# GPS_Module.net
KiCad netlist of a schematic drawn in Altium Designer
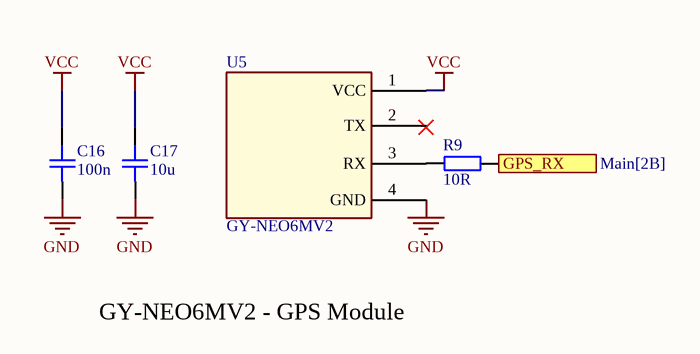
[diagram p0: GPS_Module.SchDoc]

(export (version "E")
  (design (tool "Eeschema 10.0.6"))
  (components
    (comp (ref "C16")
      (value "100n")
      (footprint "CAP_0805")
      (description "Capacitor SMD 0805")
      (libsource (lib "Schematic-Lib-PhilsLab") (part "CAP_0805"))
    )
    (comp (ref "C17")
      (value "10u")
      (footprint "CAP_0805")
      (description "Capacitor SMD 0805")
      (libsource (lib "Schematic-Lib-PhilsLab") (part "CAP_0805"))
    )
    (comp (ref "R9")
      (value "10R")
      (footprint "RES_0805")
      (description "Resistor SMD 0805")
      (libsource (lib "Schematic-Lib-PhilsLab") (part "RES_0805"))
    )
    (comp (ref "U5")
      (value "GY-NEO6MV2")
      (footprint "GY-NEO6MV")
      (libsource (lib "Schematic_Library_TM") (part "GY-NEO6MV2"))
    )
  )
  (nets
    (net (code "1") (name "/GPS_RX") (class "Default")
      (node (ref "R9") (pin "2") (pinfunction "2_2") (pintype "passive"))
    )
    (net (code "2") (name "GND") (class "Default")
      (node (ref "C16") (pin "1") (pinfunction "1_1") (pintype "passive"))
      (node (ref "C17") (pin "1") (pinfunction "1_1") (pintype "passive"))
      (node (ref "U5") (pin "4") (pinfunction "GND_4") (pintype "passive"))
    )
    (net (code "3") (name "Net-(U5-RX)") (class "Default")
      (node (ref "R9") (pin "1") (pinfunction "1_1") (pintype "passive"))
      (node (ref "U5") (pin "3") (pinfunction "RX_3") (pintype "passive"))
    )
    (net (code "4") (name "VCC") (class "Default")
      (node (ref "C16") (pin "2") (pinfunction "2_2") (pintype "passive"))
      (node (ref "C17") (pin "2") (pinfunction "2_2") (pintype "passive"))
      (node (ref "U5") (pin "1") (pinfunction "VCC_1") (pintype "passive"))
    )
    (net (code "5") (name "unconnected-(U5-TX-Pad2)") (class "Default")
      (node (ref "U5") (pin "2") (pinfunction "TX_2") (pintype "passive"))
    )
  )
)
